# tarocco-proto.net
KiCad netlist of a schematic drawn in EAGLE
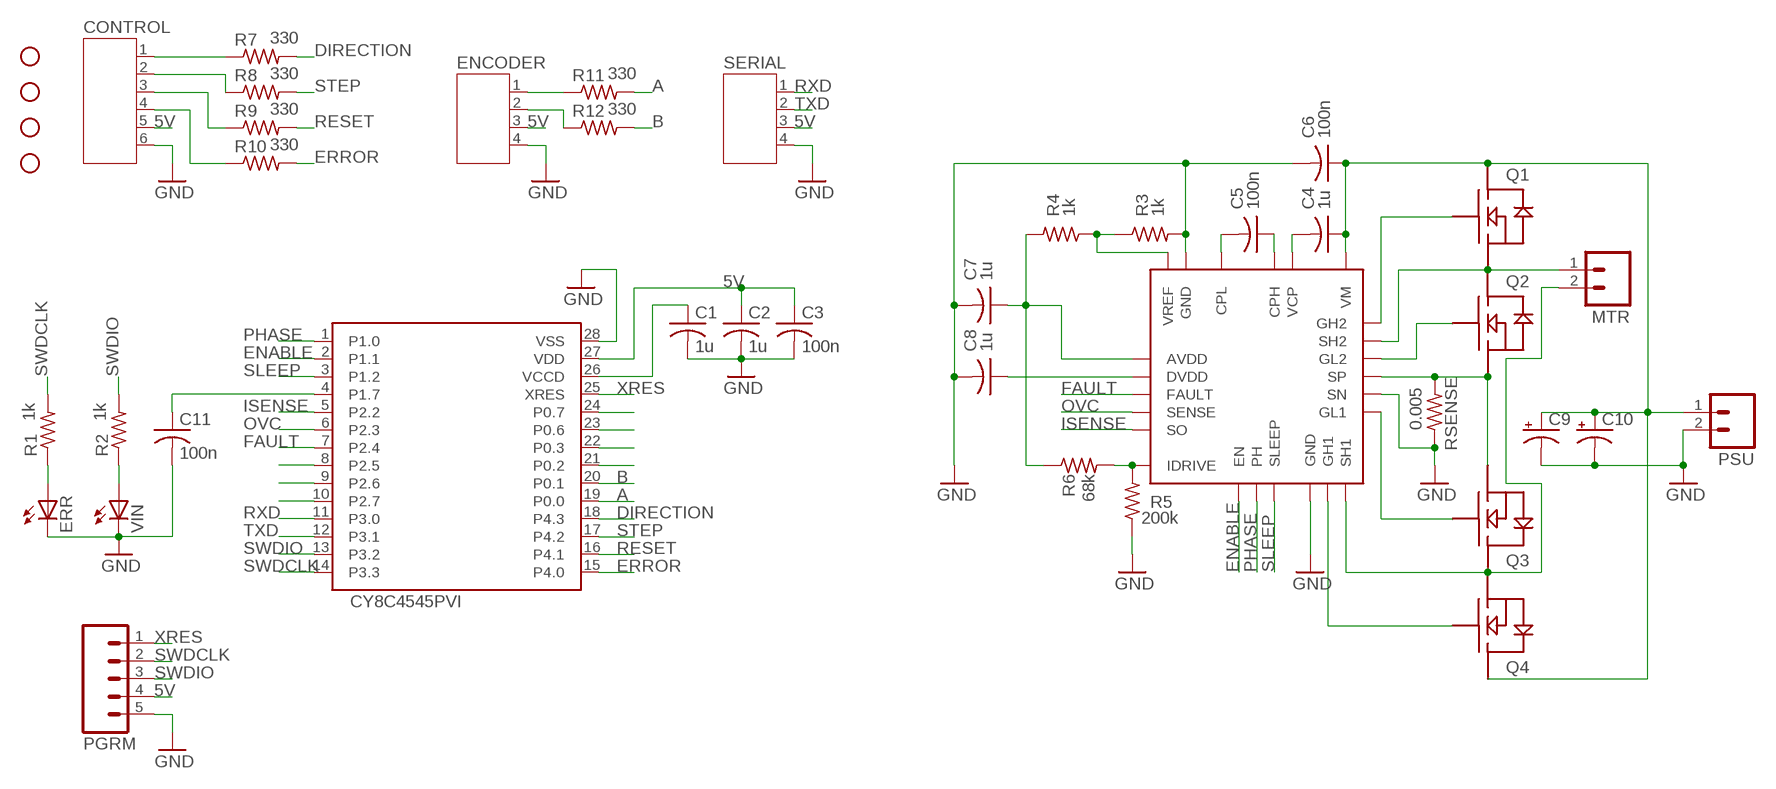
[diagram p0: schematic, sheet 1]

(export (version "E")
  (design (tool "Eeschema 10.0.6"))
  (components
    (comp (ref "8701")
      (value "DRV8701")
      (footprint "eagle-import:VQFN24")
      (libsource (lib "eagle-import") (part "DRV8701"))
    )
    (comp (ref "C1")
      (value "1u")
      (footprint "eagle-import:C0603")
      (libsource (lib "eagle-import") (part "C-USC0603"))
    )
    (comp (ref "C2")
      (value "1u")
      (footprint "eagle-import:C0603")
      (libsource (lib "eagle-import") (part "C-USC0603"))
    )
    (comp (ref "C3")
      (value "100n")
      (footprint "eagle-import:C0603")
      (libsource (lib "eagle-import") (part "C-USC0603"))
    )
    (comp (ref "C4")
      (value "1u")
      (footprint "eagle-import:C0603")
      (libsource (lib "eagle-import") (part "C-USC0603"))
    )
    (comp (ref "C5")
      (value "100n")
      (footprint "eagle-import:C0603")
      (libsource (lib "eagle-import") (part "C-USC0603"))
    )
    (comp (ref "C6")
      (value "100n")
      (footprint "eagle-import:C0603")
      (libsource (lib "eagle-import") (part "C-USC0603"))
    )
    (comp (ref "C7")
      (value "1u")
      (footprint "eagle-import:C0603")
      (libsource (lib "eagle-import") (part "C-USC0603"))
    )
    (comp (ref "C8")
      (value "1u")
      (footprint "eagle-import:C0603")
      (libsource (lib "eagle-import") (part "C-USC0603"))
    )
    (comp (ref "C9")
      (value "CPOL-USE3.5-8")
      (footprint "eagle-import:E3,5-8")
      (libsource (lib "eagle-import") (part "CPOL-USE3.5-8"))
    )
    (comp (ref "C10")
      (value "CPOL-USE3.5-8")
      (footprint "eagle-import:E3,5-8")
      (libsource (lib "eagle-import") (part "CPOL-USE3.5-8"))
    )
    (comp (ref "C11")
      (value "100n")
      (footprint "eagle-import:C0603")
      (libsource (lib "eagle-import") (part "C-USC0603"))
    )
    (comp (ref "CONTROL")
      (value "JST-PH6")
      (footprint "eagle-import:JST-PH6")
      (libsource (lib "eagle-import") (part "JST-PH6"))
    )
    (comp (ref "ENCODER")
      (value "JST-PH4")
      (footprint "eagle-import:JST-PH4")
      (libsource (lib "eagle-import") (part "JST-PH4"))
    )
    (comp (ref "ERR")
      (value "LEDCHIP-LED0603")
      (footprint "eagle-import:CHIP-LED0603")
      (libsource (lib "eagle-import") (part "LEDCHIP-LED0603"))
    )
    (comp (ref "IC1")
      (value "CY8C4545PVI")
      (footprint "eagle-import:SSOP28")
      (libsource (lib "eagle-import") (part "CY8C4545PVI"))
    )
    (comp (ref "MTR")
      (value "M023.5MM")
      (footprint "eagle-import:SCREWTERMINAL-3.5MM-2")
      (libsource (lib "eagle-import") (part "M023.5MM"))
    )
    (comp (ref "PGRM")
      (value "M05SMD2")
      (footprint "eagle-import:1X05-1MM-RA")
      (libsource (lib "eagle-import") (part "M05SMD2"))
    )
    (comp (ref "PSU")
      (value "M023.5MM")
      (footprint "eagle-import:SCREWTERMINAL-3.5MM-2")
      (libsource (lib "eagle-import") (part "M023.5MM"))
    )
    (comp (ref "Q1")
      (value "NEXFET_SINGLECSD18537NQ5A")
      (footprint "eagle-import:SON5X6")
      (libsource (lib "eagle-import") (part "NEXFET_SINGLECSD18537NQ5A"))
    )
    (comp (ref "Q2")
      (value "NEXFET_SINGLECSD18537NQ5A")
      (footprint "eagle-import:SON5X6")
      (libsource (lib "eagle-import") (part "NEXFET_SINGLECSD18537NQ5A"))
    )
    (comp (ref "Q3")
      (value "NEXFET_SINGLECSD18537NQ5A")
      (footprint "eagle-import:SON5X6")
      (libsource (lib "eagle-import") (part "NEXFET_SINGLECSD18537NQ5A"))
    )
    (comp (ref "Q4")
      (value "NEXFET_SINGLECSD18537NQ5A")
      (footprint "eagle-import:SON5X6")
      (libsource (lib "eagle-import") (part "NEXFET_SINGLECSD18537NQ5A"))
    )
    (comp (ref "R1")
      (value "1k")
      (footprint "eagle-import:R0603")
      (libsource (lib "eagle-import") (part "R-US_R0603"))
    )
    (comp (ref "R2")
      (value "1k")
      (footprint "eagle-import:R0603")
      (libsource (lib "eagle-import") (part "R-US_R0603"))
    )
    (comp (ref "R3")
      (value "1k")
      (footprint "eagle-import:R0603")
      (libsource (lib "eagle-import") (part "R-US_R0603"))
    )
    (comp (ref "R4")
      (value "1k")
      (footprint "eagle-import:R0603")
      (libsource (lib "eagle-import") (part "R-US_R0603"))
    )
    (comp (ref "R5")
      (value "200k")
      (footprint "eagle-import:R0603")
      (libsource (lib "eagle-import") (part "R-US_R0603"))
    )
    (comp (ref "R6")
      (value "68k")
      (footprint "eagle-import:R0603")
      (libsource (lib "eagle-import") (part "R-US_R0603"))
    )
    (comp (ref "R7")
      (value "330")
      (footprint "eagle-import:R0603")
      (libsource (lib "eagle-import") (part "R-US_R0603"))
    )
    (comp (ref "R8")
      (value "330")
      (footprint "eagle-import:R0603")
      (libsource (lib "eagle-import") (part "R-US_R0603"))
    )
    (comp (ref "R9")
      (value "330")
      (footprint "eagle-import:R0603")
      (libsource (lib "eagle-import") (part "R-US_R0603"))
    )
    (comp (ref "R10")
      (value "330")
      (footprint "eagle-import:R0603")
      (libsource (lib "eagle-import") (part "R-US_R0603"))
    )
    (comp (ref "R11")
      (value "330")
      (footprint "eagle-import:R0603")
      (libsource (lib "eagle-import") (part "R-US_R0603"))
    )
    (comp (ref "R12")
      (value "330")
      (footprint "eagle-import:R0603")
      (libsource (lib "eagle-import") (part "R-US_R0603"))
    )
    (comp (ref "RSENSE")
      (value "0.005")
      (footprint "eagle-import:R2512")
      (libsource (lib "eagle-import") (part "R-US_R2512"))
    )
    (comp (ref "SERIAL")
      (value "JST-PH4")
      (footprint "eagle-import:JST-PH4")
      (libsource (lib "eagle-import") (part "JST-PH4"))
    )
    (comp (ref "STANDOFF1")
      (value "STAND-OFF")
      (footprint "eagle-import:STAND-OFF")
      (libsource (lib "eagle-import") (part "STAND-OFF"))
    )
    (comp (ref "STANDOFF2")
      (value "STAND-OFF")
      (footprint "eagle-import:STAND-OFF")
      (libsource (lib "eagle-import") (part "STAND-OFF"))
    )
    (comp (ref "STANDOFF3")
      (value "STAND-OFF")
      (footprint "eagle-import:STAND-OFF")
      (libsource (lib "eagle-import") (part "STAND-OFF"))
    )
    (comp (ref "STANDOFF4")
      (value "STAND-OFF")
      (footprint "eagle-import:STAND-OFF")
      (libsource (lib "eagle-import") (part "STAND-OFF"))
    )
    (comp (ref "VIN")
      (value "LEDCHIP-LED0603")
      (footprint "eagle-import:CHIP-LED0603")
      (libsource (lib "eagle-import") (part "LEDCHIP-LED0603"))
    )
  )
  (nets
    (net (code "1") (name "/5V") (class "Default")
      (node (ref "C2") (pin "1") (pinfunction "1_1") (pintype "passive"))
      (node (ref "C3") (pin "1") (pinfunction "1_1") (pintype "passive"))
      (node (ref "CONTROL") (pin "5") (pinfunction "5_5") (pintype "passive"))
      (node (ref "ENCODER") (pin "3") (pinfunction "3_3") (pintype "passive"))
      (node (ref "IC1") (pin "27") (pinfunction "VDD_27") (pintype "power_in"))
      (node (ref "PGRM") (pin "4") (pinfunction "4_4") (pintype "passive"))
      (node (ref "SERIAL") (pin "3") (pinfunction "3_3") (pintype "passive"))
    )
    (net (code "2") (name "/A") (class "Default")
      (node (ref "IC1") (pin "19") (pinfunction "P0.0_19") (pintype "bidirectional"))
      (node (ref "R11") (pin "2") (pinfunction "2_2") (pintype "passive"))
    )
    (net (code "3") (name "/B") (class "Default")
      (node (ref "IC1") (pin "20") (pinfunction "P0.1_20") (pintype "bidirectional"))
      (node (ref "R12") (pin "2") (pinfunction "2_2") (pintype "passive"))
    )
    (net (code "4") (name "/DIRECTION") (class "Default")
      (node (ref "IC1") (pin "18") (pinfunction "P4.3_18") (pintype "bidirectional"))
      (node (ref "R7") (pin "2") (pinfunction "2_2") (pintype "passive"))
    )
    (net (code "5") (name "/ENABLE") (class "Default")
      (node (ref "8701") (pin "EN") (pinfunction "EN_EN") (pintype "bidirectional"))
      (node (ref "IC1") (pin "2") (pinfunction "P1.1_2") (pintype "bidirectional"))
    )
    (net (code "6") (name "/ERROR") (class "Default")
      (node (ref "IC1") (pin "15") (pinfunction "P4.0_15") (pintype "bidirectional"))
      (node (ref "R10") (pin "2") (pinfunction "2_2") (pintype "passive"))
    )
    (net (code "7") (name "/FAULT") (class "Default")
      (node (ref "8701") (pin "FAULT") (pinfunction "FAULT_FAULT") (pintype "bidirectional"))
      (node (ref "IC1") (pin "7") (pinfunction "P2.4_7") (pintype "bidirectional"))
    )
    (net (code "8") (name "/ISENSE") (class "Default")
      (node (ref "8701") (pin "SO") (pinfunction "SO_SO") (pintype "bidirectional"))
      (node (ref "IC1") (pin "5") (pinfunction "P2.2_5") (pintype "bidirectional"))
    )
    (net (code "9") (name "/OVC") (class "Default")
      (node (ref "8701") (pin "SENSE") (pinfunction "SENSE_SENSE") (pintype "bidirectional"))
      (node (ref "IC1") (pin "6") (pinfunction "P2.3_6") (pintype "bidirectional"))
    )
    (net (code "10") (name "/PHASE") (class "Default")
      (node (ref "8701") (pin "PH") (pinfunction "PH_PH") (pintype "bidirectional"))
      (node (ref "IC1") (pin "1") (pinfunction "P1.0_1") (pintype "bidirectional"))
    )
    (net (code "11") (name "/RESET") (class "Default")
      (node (ref "IC1") (pin "16") (pinfunction "P4.1_16") (pintype "bidirectional"))
      (node (ref "R9") (pin "2") (pinfunction "2_2") (pintype "passive"))
    )
    (net (code "12") (name "/RXD") (class "Default")
      (node (ref "IC1") (pin "11") (pinfunction "P3.0_11") (pintype "bidirectional"))
      (node (ref "SERIAL") (pin "1") (pinfunction "1_1") (pintype "passive"))
    )
    (net (code "13") (name "/SLEEP") (class "Default")
      (node (ref "8701") (pin "SLEEP") (pinfunction "SLEEP_SLEEP") (pintype "bidirectional"))
      (node (ref "IC1") (pin "3") (pinfunction "P1.2_3") (pintype "bidirectional"))
    )
    (net (code "14") (name "/STEP") (class "Default")
      (node (ref "IC1") (pin "17") (pinfunction "P4.2_17") (pintype "bidirectional"))
      (node (ref "R8") (pin "2") (pinfunction "2_2") (pintype "passive"))
    )
    (net (code "15") (name "/SWDCLK") (class "Default")
      (node (ref "IC1") (pin "14") (pinfunction "P3.3_14") (pintype "bidirectional"))
      (node (ref "PGRM") (pin "2") (pinfunction "2_2") (pintype "passive"))
      (node (ref "R1") (pin "2") (pinfunction "2_2") (pintype "passive"))
    )
    (net (code "16") (name "/SWDIO") (class "Default")
      (node (ref "IC1") (pin "13") (pinfunction "P3.2_13") (pintype "bidirectional"))
      (node (ref "PGRM") (pin "3") (pinfunction "3_3") (pintype "passive"))
      (node (ref "R2") (pin "2") (pinfunction "2_2") (pintype "passive"))
    )
    (net (code "17") (name "/TXD") (class "Default")
      (node (ref "IC1") (pin "12") (pinfunction "P3.1_12") (pintype "bidirectional"))
      (node (ref "SERIAL") (pin "2") (pinfunction "2_2") (pintype "passive"))
    )
    (net (code "18") (name "/XRES") (class "Default")
      (node (ref "IC1") (pin "25") (pinfunction "XRES_25") (pintype "bidirectional"))
      (node (ref "PGRM") (pin "1") (pinfunction "1_1") (pintype "passive"))
    )
    (net (code "19") (name "GND") (class "Default")
      (node (ref "8701") (pin "GND@1") (pinfunction "GND_GND@1") (pintype "bidirectional"))
      (node (ref "8701") (pin "GND@2") (pinfunction "GND_GND@2") (pintype "bidirectional"))
      (node (ref "8701") (pin "GND@3") (pinfunction "GND_GND@3") (pintype "bidirectional"))
      (node (ref "8701") (pin "SN") (pinfunction "SN_SN") (pintype "bidirectional"))
      (node (ref "C1") (pin "2") (pinfunction "2_2") (pintype "passive"))
      (node (ref "C10") (pin "-") (pinfunction "-_-") (pintype "passive"))
      (node (ref "C11") (pin "2") (pinfunction "2_2") (pintype "passive"))
      (node (ref "C2") (pin "2") (pinfunction "2_2") (pintype "passive"))
      (node (ref "C3") (pin "2") (pinfunction "2_2") (pintype "passive"))
      (node (ref "C6") (pin "2") (pinfunction "2_2") (pintype "passive"))
      (node (ref "C7") (pin "2") (pinfunction "2_2") (pintype "passive"))
      (node (ref "C8") (pin "2") (pinfunction "2_2") (pintype "passive"))
      (node (ref "C9") (pin "-") (pinfunction "-_-") (pintype "passive"))
      (node (ref "CONTROL") (pin "6") (pinfunction "6_6") (pintype "passive"))
      (node (ref "ENCODER") (pin "4") (pinfunction "4_4") (pintype "passive"))
      (node (ref "ERR") (pin "C") (pinfunction "C_C") (pintype "passive"))
      (node (ref "IC1") (pin "28") (pinfunction "VSS_28") (pintype "power_in"))
      (node (ref "PGRM") (pin "5") (pinfunction "5_5") (pintype "passive"))
      (node (ref "PSU") (pin "2") (pinfunction "2_2") (pintype "passive"))
      (node (ref "R3") (pin "2") (pinfunction "2_2") (pintype "passive"))
      (node (ref "R5") (pin "1") (pinfunction "1_1") (pintype "passive"))
      (node (ref "RSENSE") (pin "1") (pinfunction "1_1") (pintype "passive"))
      (node (ref "SERIAL") (pin "4") (pinfunction "4_4") (pintype "passive"))
      (node (ref "VIN") (pin "C") (pinfunction "C_C") (pintype "passive"))
    )
    (net (code "20") (name "Net-(8701-PadAVDD)") (class "Default")
      (node (ref "8701") (pin "AVDD") (pinfunction "AVDD_AVDD") (pintype "bidirectional"))
      (node (ref "C7") (pin "1") (pinfunction "1_1") (pintype "passive"))
      (node (ref "R4") (pin "2") (pinfunction "2_2") (pintype "passive"))
      (node (ref "R6") (pin "1") (pinfunction "1_1") (pintype "passive"))
    )
    (net (code "21") (name "Net-(8701-PadCPH)") (class "Default")
      (node (ref "8701") (pin "CPH") (pinfunction "CPH_CPH") (pintype "bidirectional"))
      (node (ref "C5") (pin "1") (pinfunction "1_1") (pintype "passive"))
    )
    (net (code "22") (name "Net-(8701-PadCPL)") (class "Default")
      (node (ref "8701") (pin "CPL") (pinfunction "CPL_CPL") (pintype "bidirectional"))
      (node (ref "C5") (pin "2") (pinfunction "2_2") (pintype "passive"))
    )
    (net (code "23") (name "Net-(8701-PadDVDD)") (class "Default")
      (node (ref "8701") (pin "DVDD") (pinfunction "DVDD_DVDD") (pintype "bidirectional"))
      (node (ref "C8") (pin "1") (pinfunction "1_1") (pintype "passive"))
    )
    (net (code "24") (name "Net-(8701-PadGH1)") (class "Default")
      (node (ref "8701") (pin "GH1") (pinfunction "GH1_GH1") (pintype "bidirectional"))
      (node (ref "Q4") (pin "GATE") (pinfunction "GATE_GATE") (pintype "bidirectional"))
    )
    (net (code "25") (name "Net-(8701-PadGH2)") (class "Default")
      (node (ref "8701") (pin "GH2") (pinfunction "GH2_GH2") (pintype "bidirectional"))
      (node (ref "Q1") (pin "GATE") (pinfunction "GATE_GATE") (pintype "bidirectional"))
    )
    (net (code "26") (name "Net-(8701-PadGL1)") (class "Default")
      (node (ref "8701") (pin "GL1") (pinfunction "GL1_GL1") (pintype "bidirectional"))
      (node (ref "Q3") (pin "GATE") (pinfunction "GATE_GATE") (pintype "bidirectional"))
    )
    (net (code "27") (name "Net-(8701-PadGL2)") (class "Default")
      (node (ref "8701") (pin "GL2") (pinfunction "GL2_GL2") (pintype "bidirectional"))
      (node (ref "Q2") (pin "GATE") (pinfunction "GATE_GATE") (pintype "bidirectional"))
    )
    (net (code "28") (name "Net-(8701-PadIDRIVE)") (class "Default")
      (node (ref "8701") (pin "IDRIVE") (pinfunction "IDRIVE_IDRIVE") (pintype "bidirectional"))
      (node (ref "R5") (pin "2") (pinfunction "2_2") (pintype "passive"))
      (node (ref "R6") (pin "2") (pinfunction "2_2") (pintype "passive"))
    )
    (net (code "29") (name "Net-(8701-PadSH1)") (class "Default")
      (node (ref "8701") (pin "SH1") (pinfunction "SH1_SH1") (pintype "bidirectional"))
      (node (ref "MTR") (pin "2") (pinfunction "2_2") (pintype "passive"))
      (node (ref "Q3") (pin "DRAIN@1") (pinfunction "DRAIN_DRAIN@1") (pintype "bidirectional"))
      (node (ref "Q3") (pin "DRAIN@2") (pinfunction "DRAIN_DRAIN@2") (pintype "bidirectional"))
      (node (ref "Q3") (pin "DRAIN@3") (pinfunction "DRAIN_DRAIN@3") (pintype "bidirectional"))
      (node (ref "Q3") (pin "DRAIN@4") (pinfunction "DRAIN_DRAIN@4") (pintype "bidirectional"))
      (node (ref "Q3") (pin "DRAIN@5") (pinfunction "DRAIN_DRAIN@5") (pintype "bidirectional"))
      (node (ref "Q4") (pin "SOURCE@1") (pinfunction "SOURCE_SOURCE@1") (pintype "bidirectional"))
      (node (ref "Q4") (pin "SOURCE@2") (pinfunction "SOURCE_SOURCE@2") (pintype "bidirectional"))
      (node (ref "Q4") (pin "SOURCE@3") (pinfunction "SOURCE_SOURCE@3") (pintype "bidirectional"))
    )
    (net (code "30") (name "Net-(8701-PadSH2)") (class "Default")
      (node (ref "8701") (pin "SH2") (pinfunction "SH2_SH2") (pintype "bidirectional"))
      (node (ref "MTR") (pin "1") (pinfunction "1_1") (pintype "passive"))
      (node (ref "Q1") (pin "SOURCE@1") (pinfunction "SOURCE_SOURCE@1") (pintype "bidirectional"))
      (node (ref "Q1") (pin "SOURCE@2") (pinfunction "SOURCE_SOURCE@2") (pintype "bidirectional"))
      (node (ref "Q1") (pin "SOURCE@3") (pinfunction "SOURCE_SOURCE@3") (pintype "bidirectional"))
      (node (ref "Q2") (pin "DRAIN@1") (pinfunction "DRAIN_DRAIN@1") (pintype "bidirectional"))
      (node (ref "Q2") (pin "DRAIN@2") (pinfunction "DRAIN_DRAIN@2") (pintype "bidirectional"))
      (node (ref "Q2") (pin "DRAIN@3") (pinfunction "DRAIN_DRAIN@3") (pintype "bidirectional"))
      (node (ref "Q2") (pin "DRAIN@4") (pinfunction "DRAIN_DRAIN@4") (pintype "bidirectional"))
      (node (ref "Q2") (pin "DRAIN@5") (pinfunction "DRAIN_DRAIN@5") (pintype "bidirectional"))
    )
    (net (code "31") (name "Net-(8701-PadSP)") (class "Default")
      (node (ref "8701") (pin "SP") (pinfunction "SP_SP") (pintype "bidirectional"))
      (node (ref "Q2") (pin "SOURCE@1") (pinfunction "SOURCE_SOURCE@1") (pintype "bidirectional"))
      (node (ref "Q2") (pin "SOURCE@2") (pinfunction "SOURCE_SOURCE@2") (pintype "bidirectional"))
      (node (ref "Q2") (pin "SOURCE@3") (pinfunction "SOURCE_SOURCE@3") (pintype "bidirectional"))
      (node (ref "Q3") (pin "SOURCE@1") (pinfunction "SOURCE_SOURCE@1") (pintype "bidirectional"))
      (node (ref "Q3") (pin "SOURCE@2") (pinfunction "SOURCE_SOURCE@2") (pintype "bidirectional"))
      (node (ref "Q3") (pin "SOURCE@3") (pinfunction "SOURCE_SOURCE@3") (pintype "bidirectional"))
      (node (ref "RSENSE") (pin "2") (pinfunction "2_2") (pintype "passive"))
    )
    (net (code "32") (name "Net-(8701-PadVCP)") (class "Default")
      (node (ref "8701") (pin "VCP") (pinfunction "VCP_VCP") (pintype "bidirectional"))
      (node (ref "C4") (pin "2") (pinfunction "2_2") (pintype "passive"))
    )
    (net (code "33") (name "Net-(8701-PadVM)") (class "Default")
      (node (ref "8701") (pin "VM") (pinfunction "VM_VM") (pintype "bidirectional"))
      (node (ref "C10") (pin "+") (pinfunction "+_+") (pintype "passive"))
      (node (ref "C4") (pin "1") (pinfunction "1_1") (pintype "passive"))
      (node (ref "C6") (pin "1") (pinfunction "1_1") (pintype "passive"))
      (node (ref "C9") (pin "+") (pinfunction "+_+") (pintype "passive"))
      (node (ref "PSU") (pin "1") (pinfunction "1_1") (pintype "passive"))
      (node (ref "Q1") (pin "DRAIN@1") (pinfunction "DRAIN_DRAIN@1") (pintype "bidirectional"))
      (node (ref "Q1") (pin "DRAIN@2") (pinfunction "DRAIN_DRAIN@2") (pintype "bidirectional"))
      (node (ref "Q1") (pin "DRAIN@3") (pinfunction "DRAIN_DRAIN@3") (pintype "bidirectional"))
      (node (ref "Q1") (pin "DRAIN@4") (pinfunction "DRAIN_DRAIN@4") (pintype "bidirectional"))
      (node (ref "Q1") (pin "DRAIN@5") (pinfunction "DRAIN_DRAIN@5") (pintype "bidirectional"))
      (node (ref "Q4") (pin "DRAIN@1") (pinfunction "DRAIN_DRAIN@1") (pintype "bidirectional"))
      (node (ref "Q4") (pin "DRAIN@2") (pinfunction "DRAIN_DRAIN@2") (pintype "bidirectional"))
      (node (ref "Q4") (pin "DRAIN@3") (pinfunction "DRAIN_DRAIN@3") (pintype "bidirectional"))
      (node (ref "Q4") (pin "DRAIN@4") (pinfunction "DRAIN_DRAIN@4") (pintype "bidirectional"))
      (node (ref "Q4") (pin "DRAIN@5") (pinfunction "DRAIN_DRAIN@5") (pintype "bidirectional"))
    )
    (net (code "34") (name "Net-(8701-PadVREF)") (class "Default")
      (node (ref "8701") (pin "VREF") (pinfunction "VREF_VREF") (pintype "bidirectional"))
      (node (ref "R3") (pin "1") (pinfunction "1_1") (pintype "passive"))
      (node (ref "R4") (pin "1") (pinfunction "1_1") (pintype "passive"))
    )
    (net (code "35") (name "Net-(CONTROL-Pad1)") (class "Default")
      (node (ref "CONTROL") (pin "1") (pinfunction "1_1") (pintype "passive"))
      (node (ref "R7") (pin "1") (pinfunction "1_1") (pintype "passive"))
    )
    (net (code "36") (name "Net-(CONTROL-Pad2)") (class "Default")
      (node (ref "CONTROL") (pin "2") (pinfunction "2_2") (pintype "passive"))
      (node (ref "R8") (pin "1") (pinfunction "1_1") (pintype "passive"))
    )
    (net (code "37") (name "Net-(CONTROL-Pad3)") (class "Default")
      (node (ref "CONTROL") (pin "3") (pinfunction "3_3") (pintype "passive"))
      (node (ref "R9") (pin "1") (pinfunction "1_1") (pintype "passive"))
    )
    (net (code "38") (name "Net-(CONTROL-Pad4)") (class "Default")
      (node (ref "CONTROL") (pin "4") (pinfunction "4_4") (pintype "passive"))
      (node (ref "R10") (pin "1") (pinfunction "1_1") (pintype "passive"))
    )
    (net (code "39") (name "Net-(ENCODER-Pad1)") (class "Default")
      (node (ref "ENCODER") (pin "1") (pinfunction "1_1") (pintype "passive"))
      (node (ref "R11") (pin "1") (pinfunction "1_1") (pintype "passive"))
    )
    (net (code "40") (name "Net-(ENCODER-Pad2)") (class "Default")
      (node (ref "ENCODER") (pin "2") (pinfunction "2_2") (pintype "passive"))
      (node (ref "R12") (pin "1") (pinfunction "1_1") (pintype "passive"))
    )
    (net (code "41") (name "Net-(ERR-PadA)") (class "Default")
      (node (ref "ERR") (pin "A") (pinfunction "A_A") (pintype "passive"))
      (node (ref "R1") (pin "1") (pinfunction "1_1") (pintype "passive"))
    )
    (net (code "42") (name "Net-(IC1-P1.7)") (class "Default")
      (node (ref "C11") (pin "1") (pinfunction "1_1") (pintype "passive"))
      (node (ref "IC1") (pin "4") (pinfunction "P1.7_4") (pintype "bidirectional"))
    )
    (net (code "43") (name "Net-(IC1-VCCD)") (class "Default")
      (node (ref "C1") (pin "1") (pinfunction "1_1") (pintype "passive"))
      (node (ref "IC1") (pin "26") (pinfunction "VCCD_26") (pintype "power_in"))
    )
    (net (code "44") (name "Net-(R2-Pad1)") (class "Default")
      (node (ref "R2") (pin "1") (pinfunction "1_1") (pintype "passive"))
      (node (ref "VIN") (pin "A") (pinfunction "A_A") (pintype "passive"))
    )
    (net (code "45") (name "unconnected-(IC1-P0.2-Pad21)") (class "Default")
      (node (ref "IC1") (pin "21") (pinfunction "P0.2_21") (pintype "bidirectional"))
    )
    (net (code "46") (name "unconnected-(IC1-P0.3-Pad22)") (class "Default")
      (node (ref "IC1") (pin "22") (pinfunction "P0.3_22") (pintype "bidirectional"))
    )
    (net (code "47") (name "unconnected-(IC1-P0.6-Pad23)") (class "Default")
      (node (ref "IC1") (pin "23") (pinfunction "P0.6_23") (pintype "bidirectional"))
    )
    (net (code "48") (name "unconnected-(IC1-P0.7-Pad24)") (class "Default")
      (node (ref "IC1") (pin "24") (pinfunction "P0.7_24") (pintype "bidirectional"))
    )
    (net (code "49") (name "unconnected-(IC1-P2.5-Pad8)") (class "Default")
      (node (ref "IC1") (pin "8") (pinfunction "P2.5_8") (pintype "bidirectional"))
    )
    (net (code "50") (name "unconnected-(IC1-P2.6-Pad9)") (class "Default")
      (node (ref "IC1") (pin "9") (pinfunction "P2.6_9") (pintype "bidirectional"))
    )
    (net (code "51") (name "unconnected-(IC1-P2.7-Pad10)") (class "Default")
      (node (ref "IC1") (pin "10") (pinfunction "P2.7_10") (pintype "bidirectional"))
    )
  )
)
